# Sheet_1_2025-10-29.net
KiCad netlist of a schematic drawn in Altium Designer
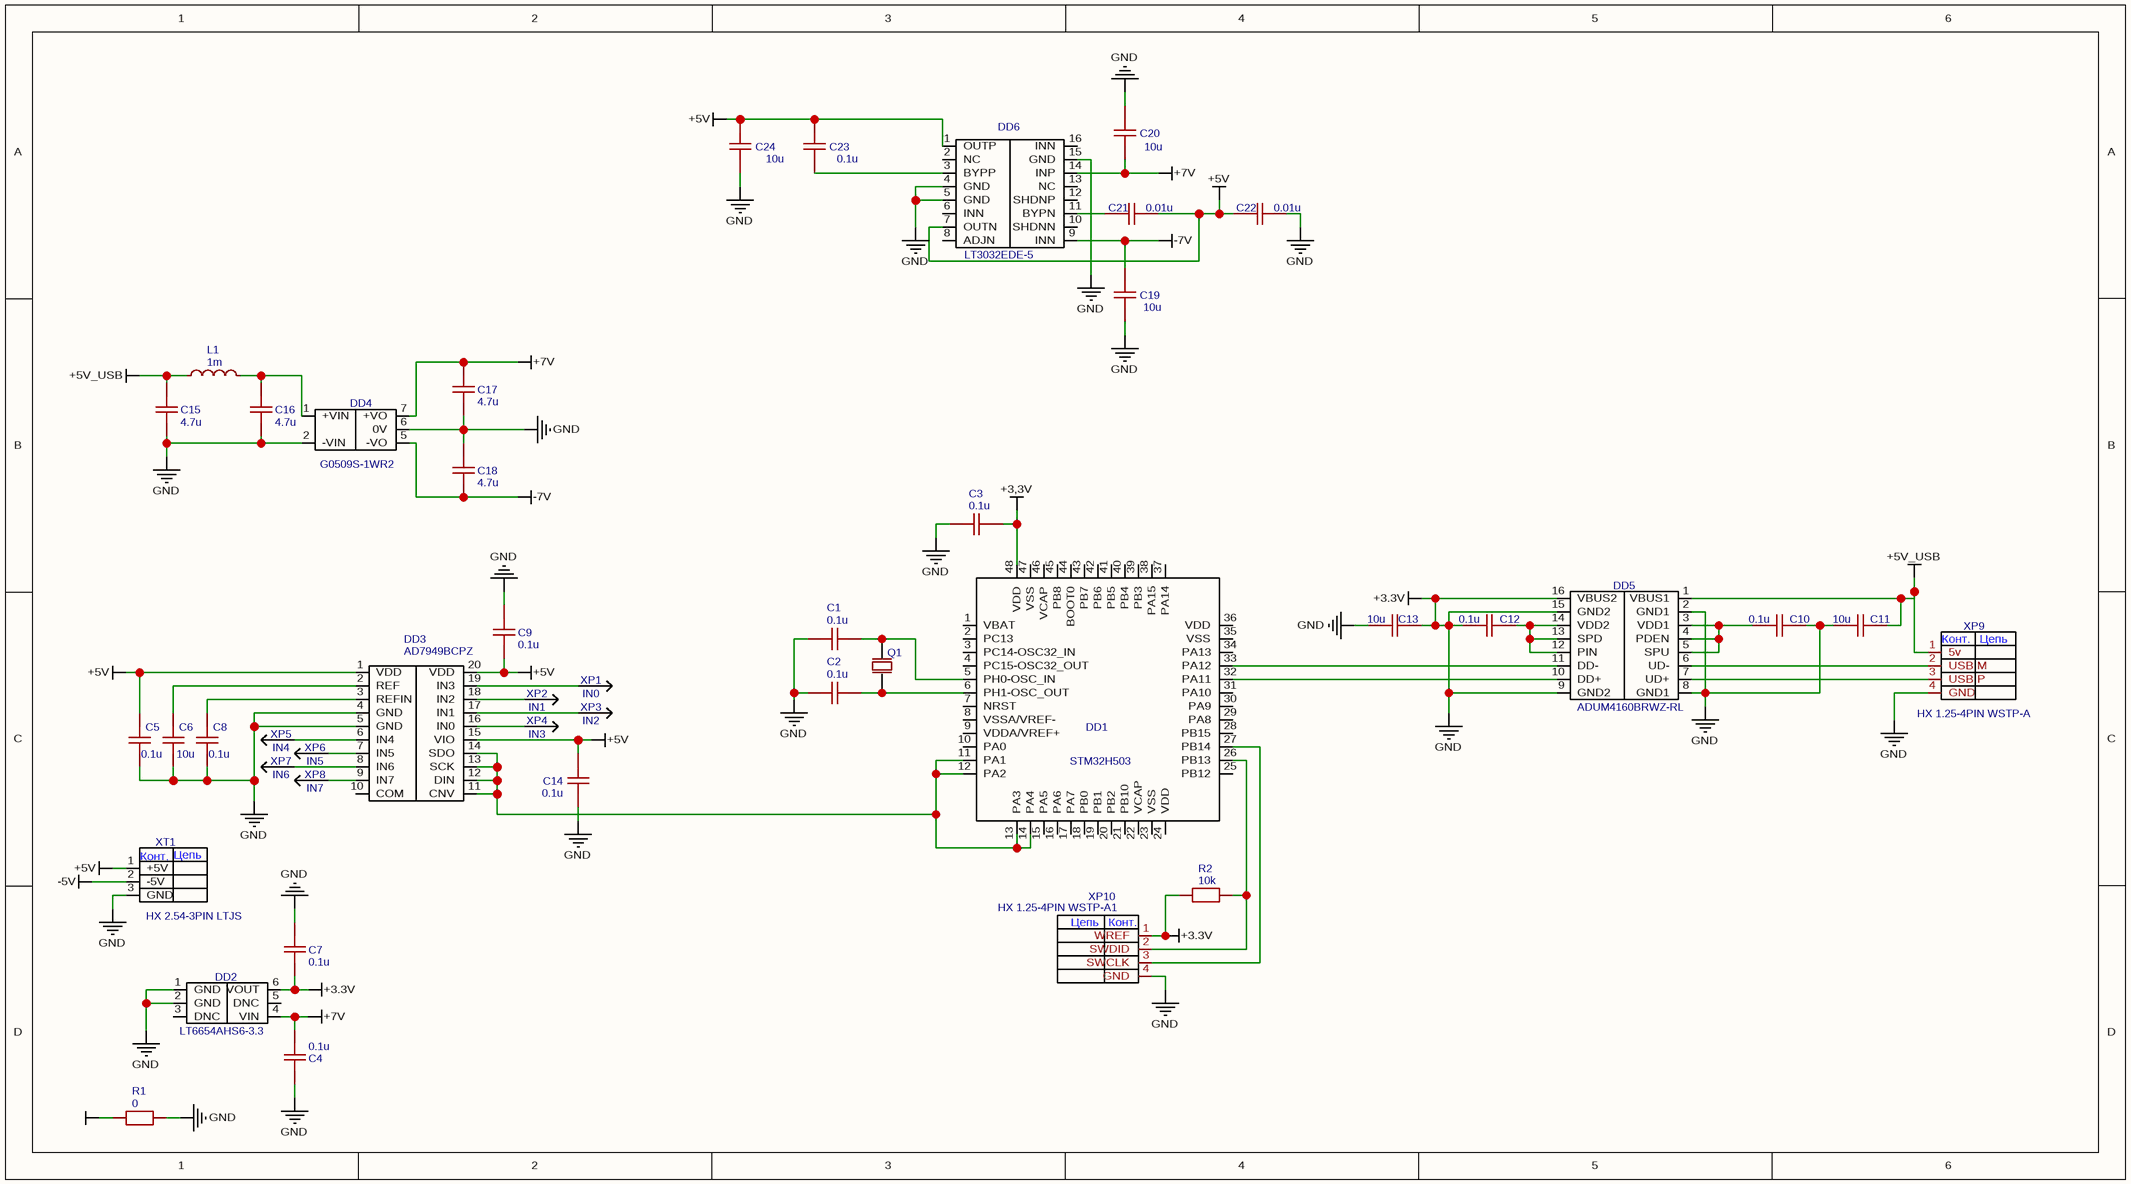
[diagram p0: Sheet_1_2025-10-29.schdoc]

(export (version "E")
  (design (tool "Eeschema 10.0.6"))
  (components
    (comp (ref "C1")
      (value "0.1u")
      (fields (field (name "CONTRIBUTOR") "LCEDA_Lib"))
      (libsource (lib "") (part "root_0_0.1u__1"))
    )
    (comp (ref "C2")
      (value "0.1u")
      (fields (field (name "CONTRIBUTOR") "LCEDA_Lib"))
      (libsource (lib "") (part "root_0_0.1u__1"))
    )
    (comp (ref "C3")
      (value "0.1u")
      (fields (field (name "CONTRIBUTOR") "LCEDA_Lib"))
      (libsource (lib "") (part "root_0_0.1u__1"))
    )
    (comp (ref "C4")
      (value "0.1u")
      (fields (field (name "CONTRIBUTOR") "LCEDA_Lib"))
      (libsource (lib "") (part "root_1_0.1u__2"))
    )
    (comp (ref "C5")
      (value "0.1u")
      (fields (field (name "CONTRIBUTOR") "LCEDA_Lib"))
      (libsource (lib "") (part "root_1_0.1u__1"))
    )
    (comp (ref "C6")
      (value "10u")
      (fields (field (name "CONTRIBUTOR") "LCEDA_Lib"))
      (libsource (lib "") (part "root_1_10u__1"))
    )
    (comp (ref "C7")
      (value "0.1u")
      (fields (field (name "CONTRIBUTOR") "LCEDA_Lib"))
      (libsource (lib "") (part "root_1_0.1u__1"))
    )
    (comp (ref "C8")
      (value "0.1u")
      (fields (field (name "CONTRIBUTOR") "LCEDA_Lib"))
      (libsource (lib "") (part "root_1_0.1u__1"))
    )
    (comp (ref "C9")
      (value "0.1u")
      (fields (field (name "CONTRIBUTOR") "LCEDA_Lib"))
      (libsource (lib "altium-import") (part "root_3_0.1u_"))
    )
    (comp (ref "C10")
      (value "0.1u")
      (fields (field (name "CONTRIBUTOR") "LCEDA_Lib"))
      (libsource (lib "altium-import") (part "root_0_0.1u_"))
    )
    (comp (ref "C11")
      (value "10u")
      (fields (field (name "CONTRIBUTOR") "LCEDA_Lib"))
      (libsource (lib "altium-import") (part "root_0_10u_"))
    )
    (comp (ref "C12")
      (value "0.1u")
      (fields (field (name "CONTRIBUTOR") "LCEDA_Lib"))
      (libsource (lib "altium-import") (part "root_0_0.1u_"))
    )
    (comp (ref "C13")
      (value "10u")
      (fields (field (name "CONTRIBUTOR") "LCEDA_Lib"))
      (libsource (lib "altium-import") (part "root_0_10u_"))
    )
    (comp (ref "C14")
      (value "0.1u")
      (fields (field (name "CONTRIBUTOR") "LCEDA_Lib"))
      (libsource (lib "altium-import") (part "root_1_0.1u_"))
    )
    (comp (ref "C15")
      (value "4.7u")
      (fields (field (name "CONTRIBUTOR") "LCEDA_Lib"))
      (libsource (lib "altium-import") (part "root_1_4.7u_"))
    )
    (comp (ref "C16")
      (value "4.7u")
      (fields (field (name "CONTRIBUTOR") "LCEDA_Lib"))
      (libsource (lib "altium-import") (part "root_1_4.7u_"))
    )
    (comp (ref "C17")
      (value "4.7u")
      (fields (field (name "CONTRIBUTOR") "LCEDA_Lib"))
      (libsource (lib "altium-import") (part "root_1_4.7u_"))
    )
    (comp (ref "C18")
      (value "4.7u")
      (fields (field (name "CONTRIBUTOR") "LCEDA_Lib"))
      (libsource (lib "altium-import") (part "root_1_4.7u_"))
    )
    (comp (ref "C19")
      (value "10u")
      (fields (field (name "CONTRIBUTOR") "LCEDA_Lib"))
      (libsource (lib "altium-import") (part "root_3_10u_"))
    )
    (comp (ref "C20")
      (value "10u")
      (fields (field (name "CONTRIBUTOR") "LCEDA_Lib"))
      (libsource (lib "altium-import") (part "root_3_10u_"))
    )
    (comp (ref "C21")
      (value "0.01u")
      (fields (field (name "CONTRIBUTOR") "LCEDA_Lib"))
      (libsource (lib "altium-import") (part "root_0_0.01u_"))
    )
    (comp (ref "C22")
      (value "0.01u")
      (fields (field (name "CONTRIBUTOR") "LCEDA_Lib"))
      (libsource (lib "altium-import") (part "root_0_0.01u_"))
    )
    (comp (ref "C23")
      (value "0.1u")
      (fields (field (name "CONTRIBUTOR") "LCEDA_Lib"))
      (libsource (lib "altium-import") (part "root_1_0.1u_"))
    )
    (comp (ref "C24")
      (value "10u")
      (fields (field (name "CONTRIBUTOR") "LCEDA_Lib"))
      (libsource (lib "altium-import") (part "root_1_10u_"))
    )
    (comp (ref "DD1")
      (value "STM32H503")
      (fields
        (field (name "MANUFACTURER") "ST(意法半导体)")
        (field (name "MANUFACTURER PART") "STM32H503CBT6")
        (field (name "CONTRIBUTOR") "dipper.paints2002")
      )
      (libsource (lib "altium-import") (part "root_0_STM32H503_"))
    )
    (comp (ref "DD2")
      (value "LT6654AHS6-3.3")
      (fields
        (field (name "MANUFACTURER") "ADI(亚德诺)")
        (field (name "MANUFACTURER PART") "LT6654AHS6-3.3#TRMPBF")
        (field (name "CONTRIBUTOR") "dipper.paints2002")
      )
      (libsource (lib "altium-import") (part "root_0_LT6654AHS6-3.3_"))
    )
    (comp (ref "DD3")
      (value "AD7949BCPZ")
      (fields (field (name "MANUFACTURER") "ADI(亚德诺)") (field (name "CONTRIBUTOR") "dipper.paints2002"))
      (libsource (lib "altium-import") (part "root_0_AD7949BCPZ_"))
    )
    (comp (ref "DD4")
      (value "G0509S-1WR2")
      (fields (field (name "MANUFACTURER") "YLPTEC(易川)") (field (name "CONTRIBUTOR") "dipper.paints2002"))
      (libsource (lib "altium-import") (part "root_0_G0509S-1WR2_"))
    )
    (comp (ref "DD5")
      (value "ADUM4160BRWZ-RL")
      (fields (field (name "CONTRIBUTOR") "dipper.paints2002"))
      (libsource (lib "altium-import") (part "root_0_ADUM4160BRWZ-RL_"))
    )
    (comp (ref "DD6")
      (value "LT3032EDE-5")
      (fields
        (field (name "MANUFACTURER") "ADI(亚德诺)")
        (field (name "MANUFACTURER PART") "LT3032EDE-5#PBF")
        (field (name "CONTRIBUTOR") "dipper.paints2002")
      )
      (libsource (lib "altium-import") (part "root_0_LT3032EDE-5_"))
    )
    (comp (ref "L1")
      (value "1m")
      (fields (field (name "CONTRIBUTOR") "LCEDA_Lib"))
      (libsource (lib "altium-import") (part "root_0_1m_"))
    )
    (comp (ref "Q1")
      (value "HC-49SMD-XTAL_MD")
      (fields (field (name "CONTRIBUTOR") "LCSC"))
      (libsource (lib "altium-import") (part "root_1_HC-49SMD-XTAL_MD_"))
    )
    (comp (ref "R1")
      (value "0")
      (fields (field (name "CONTRIBUTOR") "LCEDA_Lib"))
      (libsource (lib "altium-import") (part "root_0_0_"))
    )
    (comp (ref "R2")
      (value "10k")
      (fields (field (name "CONTRIBUTOR") "LCEDA_Lib"))
      (libsource (lib "altium-import") (part "root_0_10k_"))
    )
    (comp (ref "XP1")
      (value "IN0")
      (fields (field (name "CONTRIBUTOR") "LCEDA_Lib"))
      (libsource (lib "altium-import") (part "root_0_IN0_"))
    )
    (comp (ref "XP2")
      (value "IN1")
      (fields (field (name "CONTRIBUTOR") "LCEDA_Lib"))
      (libsource (lib "altium-import") (part "root_0_IN1_"))
    )
    (comp (ref "XP3")
      (value "IN2")
      (fields (field (name "CONTRIBUTOR") "LCEDA_Lib"))
      (libsource (lib "altium-import") (part "root_0_IN2_"))
    )
    (comp (ref "XP4")
      (value "IN3")
      (fields (field (name "CONTRIBUTOR") "LCEDA_Lib"))
      (libsource (lib "altium-import") (part "root_0_IN3_"))
    )
    (comp (ref "XP5")
      (value "IN4")
      (fields (field (name "CONTRIBUTOR") "LCEDA_Lib"))
      (libsource (lib "altium-import") (part "root_0_IN4_"))
    )
    (comp (ref "XP6")
      (value "IN5")
      (fields (field (name "CONTRIBUTOR") "LCEDA_Lib"))
      (libsource (lib "altium-import") (part "root_0_IN5_"))
    )
    (comp (ref "XP7")
      (value "IN6")
      (fields (field (name "CONTRIBUTOR") "LCEDA_Lib"))
      (libsource (lib "altium-import") (part "root_0_IN6_"))
    )
    (comp (ref "XP8")
      (value "IN7")
      (fields (field (name "CONTRIBUTOR") "LCEDA_Lib"))
      (libsource (lib "altium-import") (part "root_0_IN7_"))
    )
    (comp (ref "XP9")
      (value "HX 1.25-4PIN WSTP-A")
      (fields
        (field (name "MANUFACTURER") "hanxia(韩下)")
        (field (name "MANUFACTURER PART") "HX 1.25-4PIN WSTP")
        (field (name "CONTRIBUTOR") "dipper.paints2002")
      )
      (libsource (lib "altium-import") (part "root_0_HX 1.25-4PIN WSTP-A_"))
    )
    (comp (ref "XP10")
      (value "HX 1.25-4PIN WSTP-A1")
      (fields
        (field (name "MANUFACTURER") "hanxia(韩下)")
        (field (name "MANUFACTURER PART") "HX 1.25-4PIN WSTP")
        (field (name "CONTRIBUTOR") "dipper.paints2002")
      )
      (libsource (lib "altium-import") (part "root_0_HX 1.25-4PIN WSTP-A1_"))
    )
    (comp (ref "XT1")
      (value "HX 2.54-3PIN LTJS")
      (fields (field (name "MANUFACTURER") "hanxia(韩下)") (field (name "CONTRIBUTOR") "dipper.paints2002"))
      (libsource (lib "altium-import") (part "root_0_HX 2.54-3PIN LTJS_"))
    )
  )
  (nets
    (net (code "1") (name "+3,3V") (class "Default")
      (node (ref "C3") (pin "2") (pinfunction "2_2") (pintype "passive"))
      (node (ref "DD1") (pin "48") (pinfunction "VDD_48") (pintype "passive"))
    )
    (net (code "2") (name "+3.3V") (class "Default")
      (node (ref "C1") (pin "1") (pinfunction "1_1") (pintype "passive"))
      (node (ref "C10") (pin "1") (pinfunction "1_1") (pintype "passive"))
      (node (ref "C11") (pin "2") (pinfunction "2_2") (pintype "passive"))
      (node (ref "C12") (pin "2") (pinfunction "2_2") (pintype "passive"))
      (node (ref "C13") (pin "1") (pinfunction "1_1") (pintype "passive"))
      (node (ref "C13") (pin "2") (pinfunction "2_2") (pintype "passive"))
      (node (ref "C14") (pin "1") (pinfunction "1_1") (pintype "passive"))
      (node (ref "C15") (pin "1") (pinfunction "1_1") (pintype "passive"))
      (node (ref "C16") (pin "1") (pinfunction "1_1") (pintype "passive"))
      (node (ref "C17") (pin "1") (pinfunction "1_1") (pintype "passive"))
      (node (ref "C18") (pin "2") (pinfunction "2_2") (pintype "passive"))
      (node (ref "C19") (pin "2") (pinfunction "2_2") (pintype "passive"))
      (node (ref "C2") (pin "1") (pinfunction "1_1") (pintype "passive"))
      (node (ref "C20") (pin "1") (pinfunction "1_1") (pintype "passive"))
      (node (ref "C22") (pin "2") (pinfunction "2_2") (pintype "passive"))
      (node (ref "C24") (pin "1") (pinfunction "1_1") (pintype "passive"))
      (node (ref "C3") (pin "1") (pinfunction "1_1") (pintype "passive"))
      (node (ref "C4") (pin "2") (pinfunction "2_2") (pintype "passive"))
      (node (ref "C5") (pin "1") (pinfunction "1_1") (pintype "passive"))
      (node (ref "C6") (pin "1") (pinfunction "1_1") (pintype "passive"))
      (node (ref "C7") (pin "1") (pinfunction "1_1") (pintype "passive"))
      (node (ref "C7") (pin "2") (pinfunction "2_2") (pintype "passive"))
      (node (ref "C8") (pin "1") (pinfunction "1_1") (pintype "passive"))
      (node (ref "C9") (pin "1") (pinfunction "1_1") (pintype "passive"))
      (node (ref "DD2") (pin "1") (pinfunction "GND_1") (pintype "passive"))
      (node (ref "DD2") (pin "2") (pinfunction "GND_2") (pintype "passive"))
      (node (ref "DD2") (pin "6") (pinfunction "VOUT_6") (pintype "passive"))
      (node (ref "DD3") (pin "4") (pinfunction "GND_4") (pintype "passive"))
      (node (ref "DD3") (pin "5") (pinfunction "GND_5") (pintype "passive"))
      (node (ref "DD4") (pin "2") (pinfunction "-VIN_2") (pintype "passive"))
      (node (ref "DD4") (pin "6") (pinfunction "0V_6") (pintype "passive"))
      (node (ref "DD5") (pin "15") (pinfunction "GND2_15") (pintype "passive"))
      (node (ref "DD5") (pin "16") (pinfunction "VBUS2_16") (pintype "passive"))
      (node (ref "DD5") (pin "2") (pinfunction "GND1_2") (pintype "passive"))
      (node (ref "DD5") (pin "8") (pinfunction "GND1_8") (pintype "passive"))
      (node (ref "DD5") (pin "9") (pinfunction "GND2_9") (pintype "passive"))
      (node (ref "DD6") (pin "15") (pinfunction "GND_15") (pintype "passive"))
      (node (ref "DD6") (pin "4") (pinfunction "GND_4") (pintype "passive"))
      (node (ref "DD6") (pin "5") (pinfunction "GND_5") (pintype "passive"))
      (node (ref "R1") (pin "1") (pinfunction "1_1") (pintype "passive"))
      (node (ref "R1") (pin "2") (pinfunction "2_2") (pintype "passive"))
      (node (ref "R2") (pin "1") (pinfunction "1_1") (pintype "passive"))
      (node (ref "XP10") (pin "1") (pinfunction "WREF_1") (pintype "passive"))
      (node (ref "XP10") (pin "4") (pinfunction "GND_4") (pintype "passive"))
      (node (ref "XP9") (pin "4") (pinfunction "GND_4") (pintype "passive"))
      (node (ref "XT1") (pin "3") (pinfunction "GND_3") (pintype "passive"))
    )
    (net (code "3") (name "+5V") (class "Default")
      (node (ref "C14") (pin "2") (pinfunction "2_2") (pintype "passive"))
      (node (ref "C21") (pin "2") (pinfunction "2_2") (pintype "passive"))
      (node (ref "C22") (pin "1") (pinfunction "1_1") (pintype "passive"))
      (node (ref "C23") (pin "2") (pinfunction "2_2") (pintype "passive"))
      (node (ref "C24") (pin "2") (pinfunction "2_2") (pintype "passive"))
      (node (ref "C5") (pin "2") (pinfunction "2_2") (pintype "passive"))
      (node (ref "C9") (pin "2") (pinfunction "2_2") (pintype "passive"))
      (node (ref "DD3") (pin "1") (pinfunction "VDD_1") (pintype "passive"))
      (node (ref "DD3") (pin "15") (pinfunction "VIO_15") (pintype "passive"))
      (node (ref "DD3") (pin "20") (pinfunction "VDD_20") (pintype "passive"))
      (node (ref "DD6") (pin "1") (pinfunction "OUTP_1") (pintype "passive"))
      (node (ref "DD6") (pin "7") (pinfunction "OUTN_7") (pintype "passive"))
      (node (ref "XT1") (pin "1") (pinfunction "+5V_1") (pintype "passive"))
    )
    (net (code "4") (name "+5V_USB") (class "Default")
      (node (ref "C11") (pin "1") (pinfunction "1_1") (pintype "passive"))
      (node (ref "C15") (pin "2") (pinfunction "2_2") (pintype "passive"))
      (node (ref "DD5") (pin "1") (pinfunction "VBUS1_1") (pintype "passive"))
      (node (ref "L1") (pin "1") (pinfunction "1_1") (pintype "passive"))
      (node (ref "XP9") (pin "1") (pinfunction "5v_1") (pintype "passive"))
    )
    (net (code "5") (name "+7V") (class "Default")
      (node (ref "C17") (pin "2") (pinfunction "2_2") (pintype "passive"))
      (node (ref "C20") (pin "2") (pinfunction "2_2") (pintype "passive"))
      (node (ref "C4") (pin "1") (pinfunction "1_1") (pintype "passive"))
      (node (ref "DD2") (pin "4") (pinfunction "VIN_4") (pintype "passive"))
      (node (ref "DD4") (pin "7") (pinfunction "+VO_7") (pintype "passive"))
      (node (ref "DD6") (pin "14") (pinfunction "INP_14") (pintype "passive"))
    )
    (net (code "6") (name "-5V") (class "Default")
      (node (ref "XT1") (pin "2") (pinfunction "-5V_2") (pintype "passive"))
    )
    (net (code "7") (name "-7V") (class "Default")
      (node (ref "C18") (pin "1") (pinfunction "1_1") (pintype "passive"))
      (node (ref "C19") (pin "1") (pinfunction "1_1") (pintype "passive"))
      (node (ref "DD4") (pin "5") (pinfunction "-VO_5") (pintype "passive"))
      (node (ref "DD6") (pin "9") (pinfunction "INN_9") (pintype "passive"))
    )
    (net (code "8") (name "Net-(DD1-PA1)") (class "Default")
      (node (ref "DD1") (pin "11") (pinfunction "PA1_11") (pintype "passive"))
      (node (ref "DD1") (pin "12") (pinfunction "PA2_12") (pintype "passive"))
      (node (ref "DD1") (pin "13") (pinfunction "PA3_13") (pintype "passive"))
      (node (ref "DD1") (pin "14") (pinfunction "PA4_14") (pintype "passive"))
      (node (ref "DD3") (pin "11") (pinfunction "CNV_11") (pintype "passive"))
      (node (ref "DD3") (pin "12") (pinfunction "DIN_12") (pintype "passive"))
      (node (ref "DD3") (pin "13") (pinfunction "SCK_13") (pintype "passive"))
      (node (ref "DD3") (pin "14") (pinfunction "SDO_14") (pintype "passive"))
    )
    (net (code "9") (name "Net-(DD1-PA11)") (class "Default")
      (node (ref "DD1") (pin "32") (pinfunction "PA11_32") (pintype "passive"))
      (node (ref "DD5") (pin "10") (pinfunction "DD+_10") (pintype "passive"))
    )
    (net (code "10") (name "Net-(DD1-PA12)") (class "Default")
      (node (ref "DD1") (pin "33") (pinfunction "PA12_33") (pintype "passive"))
      (node (ref "DD5") (pin "11") (pinfunction "DD-_11") (pintype "passive"))
    )
    (net (code "11") (name "Net-(DD1-PB13)") (class "Default")
      (node (ref "DD1") (pin "26") (pinfunction "PB13_26") (pintype "passive"))
      (node (ref "R2") (pin "2") (pinfunction "2_2") (pintype "passive"))
      (node (ref "XP10") (pin "2") (pinfunction "SWDID_2") (pintype "passive"))
    )
    (net (code "12") (name "Net-(DD1-PB14)") (class "Default")
      (node (ref "DD1") (pin "27") (pinfunction "PB14_27") (pintype "passive"))
      (node (ref "XP10") (pin "3") (pinfunction "SWCLK_3") (pintype "passive"))
    )
    (net (code "13") (name "Net-(DD1-PH0-OSC_IN)") (class "Default")
      (node (ref "C1") (pin "2") (pinfunction "2_2") (pintype "passive"))
      (node (ref "DD1") (pin "5") (pinfunction "PH0-OSC_IN_5") (pintype "passive"))
      (node (ref "Q1") (pin "1") (pinfunction "OSC1_1") (pintype "passive"))
    )
    (net (code "14") (name "Net-(DD1-PH1-OSC_OUT)") (class "Default")
      (node (ref "C2") (pin "2") (pinfunction "2_2") (pintype "passive"))
      (node (ref "DD1") (pin "6") (pinfunction "PH1-OSC_OUT_6") (pintype "passive"))
      (node (ref "Q1") (pin "2") (pinfunction "OSC2_2") (pintype "passive"))
    )
    (net (code "15") (name "Net-(DD3-IN0)") (class "Default")
      (node (ref "DD3") (pin "16") (pinfunction "IN0_16") (pintype "passive"))
      (node (ref "XP4") (pin "1") (pinfunction "1_1") (pintype "passive"))
    )
    (net (code "16") (name "Net-(DD3-IN1)") (class "Default")
      (node (ref "DD3") (pin "17") (pinfunction "IN1_17") (pintype "passive"))
      (node (ref "XP3") (pin "1") (pinfunction "1_1") (pintype "passive"))
    )
    (net (code "17") (name "Net-(DD3-IN2)") (class "Default")
      (node (ref "DD3") (pin "18") (pinfunction "IN2_18") (pintype "passive"))
      (node (ref "XP2") (pin "1") (pinfunction "1_1") (pintype "passive"))
    )
    (net (code "18") (name "Net-(DD3-IN3)") (class "Default")
      (node (ref "DD3") (pin "19") (pinfunction "IN3_19") (pintype "passive"))
      (node (ref "XP1") (pin "1") (pinfunction "1_1") (pintype "passive"))
    )
    (net (code "19") (name "Net-(DD3-IN4)") (class "Default")
      (node (ref "DD3") (pin "6") (pinfunction "IN4_6") (pintype "passive"))
      (node (ref "XP5") (pin "1") (pinfunction "1_1") (pintype "passive"))
    )
    (net (code "20") (name "Net-(DD3-IN5)") (class "Default")
      (node (ref "DD3") (pin "7") (pinfunction "IN5_7") (pintype "passive"))
      (node (ref "XP6") (pin "1") (pinfunction "1_1") (pintype "passive"))
    )
    (net (code "21") (name "Net-(DD3-IN6)") (class "Default")
      (node (ref "DD3") (pin "8") (pinfunction "IN6_8") (pintype "passive"))
      (node (ref "XP7") (pin "1") (pinfunction "1_1") (pintype "passive"))
    )
    (net (code "22") (name "Net-(DD3-IN7)") (class "Default")
      (node (ref "DD3") (pin "9") (pinfunction "IN7_9") (pintype "passive"))
      (node (ref "XP8") (pin "1") (pinfunction "1_1") (pintype "passive"))
    )
    (net (code "23") (name "Net-(DD3-REF)") (class "Default")
      (node (ref "C6") (pin "2") (pinfunction "2_2") (pintype "passive"))
      (node (ref "DD3") (pin "2") (pinfunction "REF_2") (pintype "passive"))
    )
    (net (code "24") (name "Net-(DD3-REFIN)") (class "Default")
      (node (ref "C8") (pin "2") (pinfunction "2_2") (pintype "passive"))
      (node (ref "DD3") (pin "3") (pinfunction "REFIN_3") (pintype "passive"))
    )
    (net (code "25") (name "Net-(DD4-+VIN)") (class "Default")
      (node (ref "C16") (pin "2") (pinfunction "2_2") (pintype "passive"))
      (node (ref "DD4") (pin "1") (pinfunction "+VIN_1") (pintype "passive"))
      (node (ref "L1") (pin "2") (pinfunction "2_2") (pintype "passive"))
    )
    (net (code "26") (name "Net-(DD5-PDEN)") (class "Default")
      (node (ref "C10") (pin "2") (pinfunction "2_2") (pintype "passive"))
      (node (ref "DD5") (pin "3") (pinfunction "VDD1_3") (pintype "passive"))
      (node (ref "DD5") (pin "4") (pinfunction "PDEN_4") (pintype "passive"))
      (node (ref "DD5") (pin "5") (pinfunction "SPU_5") (pintype "passive"))
    )
    (net (code "27") (name "Net-(DD5-PIN)") (class "Default")
      (node (ref "C12") (pin "1") (pinfunction "1_1") (pintype "passive"))
      (node (ref "DD5") (pin "12") (pinfunction "PIN_12") (pintype "passive"))
      (node (ref "DD5") (pin "13") (pinfunction "SPD_13") (pintype "passive"))
      (node (ref "DD5") (pin "14") (pinfunction "VDD2_14") (pintype "passive"))
    )
    (net (code "28") (name "Net-(DD5-UD+)") (class "Default")
      (node (ref "DD5") (pin "7") (pinfunction "UD+_7") (pintype "passive"))
      (node (ref "XP9") (pin "3") (pinfunction "USB_P_3") (pintype "passive"))
    )
    (net (code "29") (name "Net-(DD5-UD-)") (class "Default")
      (node (ref "DD5") (pin "6") (pinfunction "UD-_6") (pintype "passive"))
      (node (ref "XP9") (pin "2") (pinfunction "USB_M_2") (pintype "passive"))
    )
    (net (code "30") (name "Net-(DD6-BYPN)") (class "Default")
      (node (ref "C21") (pin "1") (pinfunction "1_1") (pintype "passive"))
      (node (ref "DD6") (pin "11") (pinfunction "BYPN_11") (pintype "passive"))
    )
    (net (code "31") (name "Net-(DD6-BYPP)") (class "Default")
      (node (ref "C23") (pin "1") (pinfunction "1_1") (pintype "passive"))
      (node (ref "DD6") (pin "3") (pinfunction "BYPP_3") (pintype "passive"))
    )
    (net (code "32") (name "unconnected-(DD1-BOOT0-Pad44)") (class "Default")
      (node (ref "DD1") (pin "44") (pinfunction "BOOT0_44") (pintype "passive"))
    )
    (net (code "33") (name "unconnected-(DD1-NRST-Pad7)") (class "Default")
      (node (ref "DD1") (pin "7") (pinfunction "NRST_7") (pintype "passive"))
    )
    (net (code "34") (name "unconnected-(DD1-PA0-Pad10)") (class "Default")
      (node (ref "DD1") (pin "10") (pinfunction "PA0_10") (pintype "passive"))
    )
    (net (code "35") (name "unconnected-(DD1-PA5-Pad15)") (class "Default")
      (node (ref "DD1") (pin "15") (pinfunction "PA5_15") (pintype "passive"))
    )
    (net (code "36") (name "unconnected-(DD1-PA6-Pad16)") (class "Default")
      (node (ref "DD1") (pin "16") (pinfunction "PA6_16") (pintype "passive"))
    )
    (net (code "37") (name "unconnected-(DD1-PA7-Pad17)") (class "Default")
      (node (ref "DD1") (pin "17") (pinfunction "PA7_17") (pintype "passive"))
    )
    (net (code "38") (name "unconnected-(DD1-PA8-Pad29)") (class "Default")
      (node (ref "DD1") (pin "29") (pinfunction "PA8_29") (pintype "passive"))
    )
    (net (code "39") (name "unconnected-(DD1-PA9-Pad30)") (class "Default")
      (node (ref "DD1") (pin "30") (pinfunction "PA9_30") (pintype "passive"))
    )
    (net (code "40") (name "unconnected-(DD1-PA10-Pad31)") (class "Default")
      (node (ref "DD1") (pin "31") (pinfunction "PA10_31") (pintype "passive"))
    )
    (net (code "41") (name "unconnected-(DD1-PA13-Pad34)") (class "Default")
      (node (ref "DD1") (pin "34") (pinfunction "PA13_34") (pintype "passive"))
    )
    (net (code "42") (name "unconnected-(DD1-PA14-Pad37)") (class "Default")
      (node (ref "DD1") (pin "37") (pinfunction "PA14_37") (pintype "passive"))
    )
    (net (code "43") (name "unconnected-(DD1-PA15-Pad38)") (class "Default")
      (node (ref "DD1") (pin "38") (pinfunction "PA15_38") (pintype "passive"))
    )
    (net (code "44") (name "unconnected-(DD1-PB0-Pad18)") (class "Default")
      (node (ref "DD1") (pin "18") (pinfunction "PB0_18") (pintype "passive"))
    )
    (net (code "45") (name "unconnected-(DD1-PB1-Pad19)") (class "Default")
      (node (ref "DD1") (pin "19") (pinfunction "PB1_19") (pintype "passive"))
    )
    (net (code "46") (name "unconnected-(DD1-PB2-Pad20)") (class "Default")
      (node (ref "DD1") (pin "20") (pinfunction "PB2_20") (pintype "passive"))
    )
    (net (code "47") (name "unconnected-(DD1-PB3-Pad39)") (class "Default")
      (node (ref "DD1") (pin "39") (pinfunction "PB3_39") (pintype "passive"))
    )
    (net (code "48") (name "unconnected-(DD1-PB4-Pad40)") (class "Default")
      (node (ref "DD1") (pin "40") (pinfunction "PB4_40") (pintype "passive"))
    )
    (net (code "49") (name "unconnected-(DD1-PB5-Pad41)") (class "Default")
      (node (ref "DD1") (pin "41") (pinfunction "PB5_41") (pintype "passive"))
    )
    (net (code "50") (name "unconnected-(DD1-PB6-Pad42)") (class "Default")
      (node (ref "DD1") (pin "42") (pinfunction "PB6_42") (pintype "passive"))
    )
    (net (code "51") (name "unconnected-(DD1-PB7-Pad43)") (class "Default")
      (node (ref "DD1") (pin "43") (pinfunction "PB7_43") (pintype "passive"))
    )
    (net (code "52") (name "unconnected-(DD1-PB8-Pad45)") (class "Default")
      (node (ref "DD1") (pin "45") (pinfunction "PB8_45") (pintype "passive"))
    )
    (net (code "53") (name "unconnected-(DD1-PB10-Pad21)") (class "Default")
      (node (ref "DD1") (pin "21") (pinfunction "PB10_21") (pintype "passive"))
    )
    (net (code "54") (name "unconnected-(DD1-PB12-Pad25)") (class "Default")
      (node (ref "DD1") (pin "25") (pinfunction "PB12_25") (pintype "passive"))
    )
    (net (code "55") (name "unconnected-(DD1-PB15-Pad28)") (class "Default")
      (node (ref "DD1") (pin "28") (pinfunction "PB15_28") (pintype "passive"))
    )
    (net (code "56") (name "unconnected-(DD1-PC13-Pad2)") (class "Default")
      (node (ref "DD1") (pin "2") (pinfunction "PC13_2") (pintype "passive"))
    )
    (net (code "57") (name "unconnected-(DD1-PC14-OSC32_IN-Pad3)") (class "Default")
      (node (ref "DD1") (pin "3") (pinfunction "PC14-OSC32_IN_3") (pintype "passive"))
    )
    (net (code "58") (name "unconnected-(DD1-PC15-OSC32_OUT-Pad4)") (class "Default")
      (node (ref "DD1") (pin "4") (pinfunction "PC15-OSC32_OUT_4") (pintype "passive"))
    )
    (net (code "59") (name "unconnected-(DD1-VBAT-Pad1)") (class "Default")
      (node (ref "DD1") (pin "1") (pinfunction "VBAT_1") (pintype "passive"))
    )
    (net (code "60") (name "unconnected-(DD1-VCAP-Pad22)") (class "Default")
      (node (ref "DD1") (pin "22") (pinfunction "VCAP_22") (pintype "passive"))
    )
    (net (code "61") (name "unconnected-(DD1-VCAP-Pad46)") (class "Default")
      (node (ref "DD1") (pin "46") (pinfunction "VCAP_46") (pintype "passive"))
    )
    (net (code "62") (name "unconnected-(DD1-VDD-Pad24)") (class "Default")
      (node (ref "DD1") (pin "24") (pinfunction "VDD_24") (pintype "passive"))
    )
    (net (code "63") (name "unconnected-(DD1-VDD-Pad36)") (class "Default")
      (node (ref "DD1") (pin "36") (pinfunction "VDD_36") (pintype "passive"))
    )
    (net (code "64") (name "unconnected-(DD1-VDDA{slash}VREF+-Pad9)") (class "Default")
      (node (ref "DD1") (pin "9") (pinfunction "VDDA/VREF+_9") (pintype "passive"))
    )
    (net (code "65") (name "unconnected-(DD1-VSS-Pad23)") (class "Default")
      (node (ref "DD1") (pin "23") (pinfunction "VSS_23") (pintype "passive"))
    )
    (net (code "66") (name "unconnected-(DD1-VSS-Pad35)") (class "Default")
      (node (ref "DD1") (pin "35") (pinfunction "VSS_35") (pintype "passive"))
    )
    (net (code "67") (name "unconnected-(DD1-VSS-Pad47)") (class "Default")
      (node (ref "DD1") (pin "47") (pinfunction "VSS_47") (pintype "passive"))
    )
    (net (code "68") (name "unconnected-(DD1-VSSA{slash}VREF--Pad8)") (class "Default")
      (node (ref "DD1") (pin "8") (pinfunction "VSSA/VREF-_8") (pintype "passive"))
    )
    (net (code "69") (name "unconnected-(DD2-DNC-Pad3)") (class "Default")
      (node (ref "DD2") (pin "3") (pinfunction "DNC_3") (pintype "passive"))
    )
    (net (code "70") (name "unconnected-(DD2-DNC-Pad5)") (class "Default")
      (node (ref "DD2") (pin "5") (pinfunction "DNC_5") (pintype "passive"))
    )
    (net (code "71") (name "unconnected-(DD3-COM-Pad10)") (class "Default")
      (node (ref "DD3") (pin "10") (pinfunction "COM_10") (pintype "passive"))
    )
    (net (code "72") (name "unconnected-(DD6-ADJN-Pad8)") (class "Default")
      (node (ref "DD6") (pin "8") (pinfunction "ADJN_8") (pintype "passive"))
    )
    (net (code "73") (name "unconnected-(DD6-INN-Pad6)") (class "Default")
      (node (ref "DD6") (pin "6") (pinfunction "INN_6") (pintype "passive"))
    )
    (net (code "74") (name "unconnected-(DD6-INN-Pad16)") (class "Default")
      (node (ref "DD6") (pin "16") (pinfunction "INN_16") (pintype "passive"))
    )
    (net (code "75") (name "unconnected-(DD6-NC-Pad2)") (class "Default")
      (node (ref "DD6") (pin "2") (pinfunction "NC_2") (pintype "passive"))
    )
    (net (code "76") (name "unconnected-(DD6-NC-Pad13)") (class "Default")
      (node (ref "DD6") (pin "13") (pinfunction "NC_13") (pintype "passive"))
    )
    (net (code "77") (name "unconnected-(DD6-SHDNN-Pad10)") (class "Default")
      (node (ref "DD6") (pin "10") (pinfunction "SHDNN_10") (pintype "passive"))
    )
    (net (code "78") (name "unconnected-(DD6-SHDNP-Pad12)") (class "Default")
      (node (ref "DD6") (pin "12") (pinfunction "SHDNP_12") (pintype "passive"))
    )
  )
)
